# MM32_Class_board_V2_0.net
KiCad netlist of a schematic drawn in Altium Designer
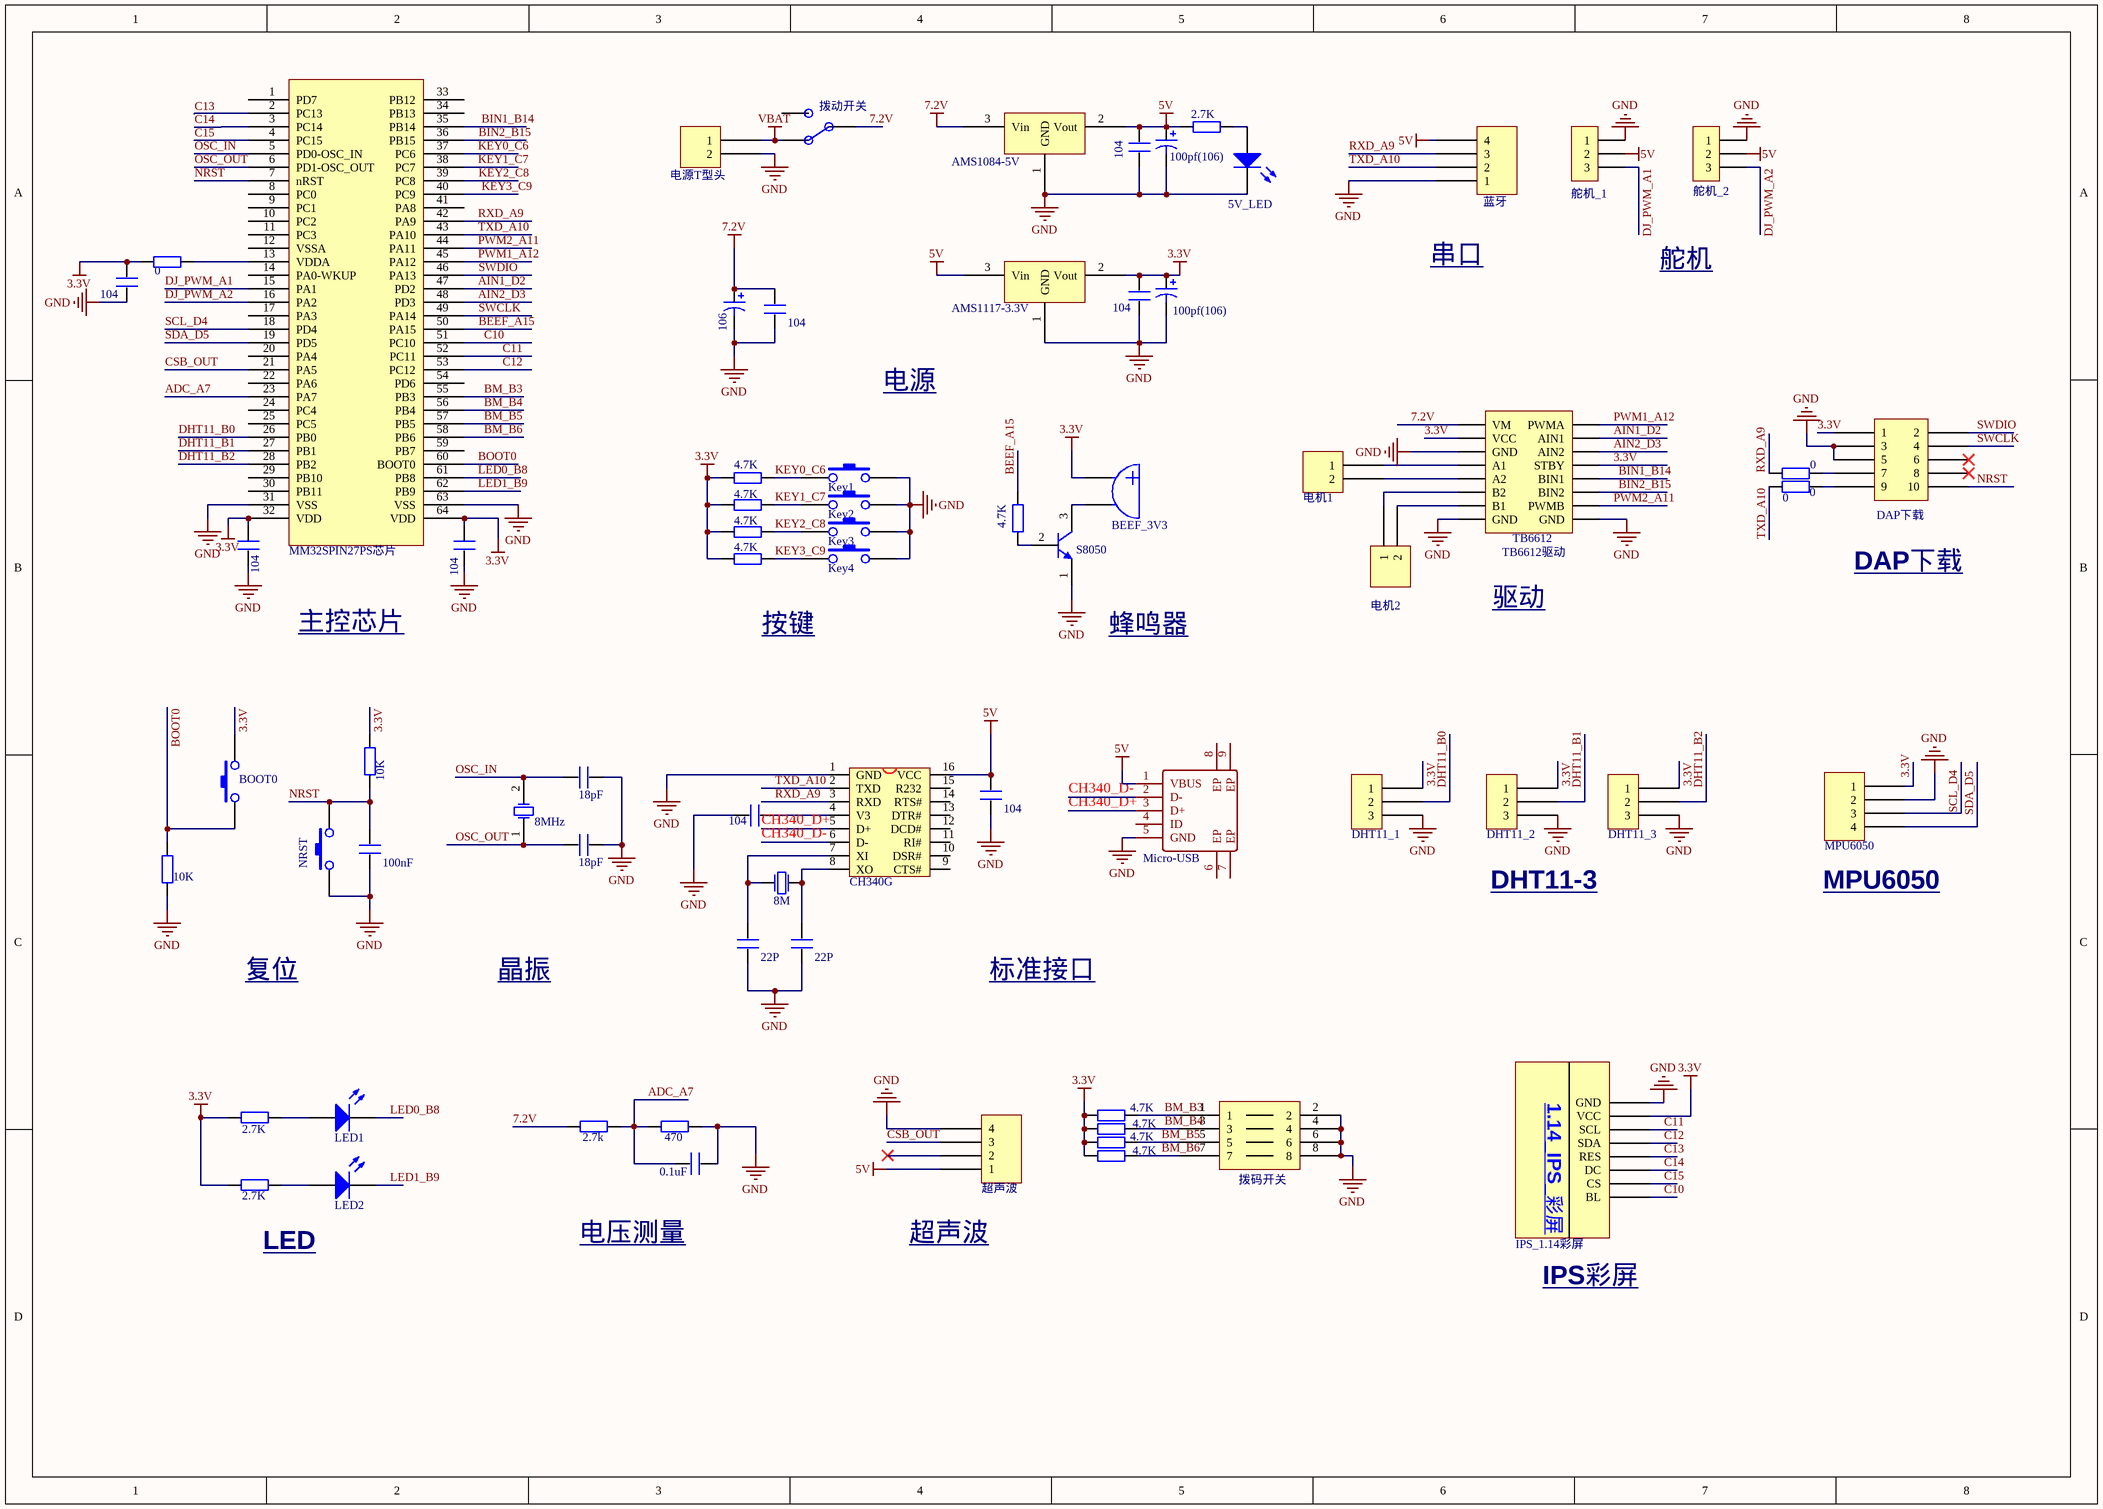
[diagram p0: MM32_Class_board_V2.0.SchDoc]

(export (version "E")
  (design (tool "Eeschema 10.0.6"))
  (components
    (comp (ref "*1")
      (value "IPS_1.14彩屏")
      (footprint "1.14_IPS")
      (libsource (lib "DZB原理图库") (part "IPS_1.14彩屏"))
    )
    (comp (ref "6050")
      (value "MPU6050")
      (footprint "四脚插座")
      (description "四脚插座")
      (libsource (lib "") (part "P4_1"))
    )
    (comp (ref "A1")
      (value "AMS1117-3.3V")
      (footprint "AMS1117")
      (libsource (lib "DZB原理图库") (part "AMS1117"))
    )
    (comp (ref "A2")
      (value "AMS1084-5V")
      (footprint "AMS1086")
      (description "5.0V")
      (libsource (lib "DZB原理图库") (part "AMS1084"))
    )
    (comp (ref "B1") (value "BEEF_3V3") (footprint "BEEF_3V3") (libsource (lib "DZB原理图库") (part "BEEF_3V3")))
    (comp (ref "BOOT0")
      (value "BOOT0")
      (footprint "贴片按键")
      (description "按键")
      (libsource (lib "DZB原理图库") (part "Key"))
    )
    (comp (ref "C1")
      (value "104")
      (footprint "电容0805")
      (description "贴片电容")
      (libsource (lib "DZB原理图库") (part "C电容"))
    )
    (comp (ref "C2")
      (value "100pf(106)")
      (footprint "钽电容1206")
      (description "钽电容")
      (fields (field (name "PUBLISHER") "Altium Limited"))
      (libsource (lib "DZB原理图库") (part "C极性电容"))
    )
    (comp (ref "C3")
      (value "104")
      (footprint "电容0805")
      (description "贴片电容")
      (libsource (lib "DZB原理图库") (part "C电容"))
    )
    (comp (ref "C4")
      (value "104")
      (footprint "电容0805")
      (description "贴片电容")
      (libsource (lib "DZB原理图库") (part "C电容"))
    )
    (comp (ref "C5")
      (value "100pf(106)")
      (footprint "钽电容1206")
      (description "钽电容")
      (fields (field (name "PUBLISHER") "Altium Limited"))
      (libsource (lib "DZB原理图库") (part "C极性电容"))
    )
    (comp (ref "C6")
      (value "106")
      (footprint "钽电容1206")
      (description "钽电容")
      (fields (field (name "PUBLISHER") "Altium Limited"))
      (libsource (lib "DZB原理图库") (part "C极性电容"))
    )
    (comp (ref "C7")
      (value "104")
      (footprint "电容0805")
      (description "贴片电容")
      (libsource (lib "DZB原理图库") (part "C电容"))
    )
    (comp (ref "C8")
      (value "104")
      (footprint "电容0805")
      (description "贴片电容")
      (libsource (lib "DZB原理图库") (part "C电容"))
    )
    (comp (ref "C9")
      (value "104")
      (footprint "电容0805")
      (description "贴片电容")
      (libsource (lib "DZB原理图库") (part "C电容"))
    )
    (comp (ref "C10")
      (value "18pF")
      (footprint "电容0805")
      (description "贴片电容")
      (libsource (lib "DZB原理图库") (part "C电容"))
    )
    (comp (ref "C11")
      (value "104")
      (footprint "电容0805")
      (description "贴片电容")
      (libsource (lib "LYF") (part "C电容"))
    )
    (comp (ref "C12")
      (value "104")
      (footprint "电容0805")
      (description "贴片电容")
      (libsource (lib "LYF") (part "C电容"))
    )
    (comp (ref "C13")
      (value "18pF")
      (footprint "电容0805")
      (description "贴片电容")
      (libsource (lib "DZB原理图库") (part "C电容"))
    )
    (comp (ref "C15")
      (value "22P")
      (footprint "电容0805")
      (description "贴片电容")
      (libsource (lib "LYF") (part "C电容"))
    )
    (comp (ref "C16")
      (value "22P")
      (footprint "电容0805")
      (description "贴片电容")
      (libsource (lib "LYF") (part "C电容"))
    )
    (comp (ref "C17")
      (value "0.1uF")
      (footprint "电容0805")
      (description "贴片电容")
      (libsource (lib "DZB原理图库") (part "C电容"))
    )
    (comp (ref "D1")
      (value "5V_LED")
      (footprint "LED贴片")
      (description "Typical RED, GREEN, YELLOW, AMBER GaAs LED")
      (fields (field (name "PUBLISHER") "Altium Limited"))
      (libsource (lib "DZB原理图库") (part "LED"))
    )
    (comp (ref "D2")
      (value "LED1")
      (footprint "LED贴片")
      (description "Typical RED, GREEN, YELLOW, AMBER GaAs LED")
      (fields (field (name "PUBLISHER") "Altium Limited"))
      (libsource (lib "DZB原理图库") (part "LED"))
    )
    (comp (ref "D3")
      (value "LED2")
      (footprint "LED贴片")
      (description "Typical RED, GREEN, YELLOW, AMBER GaAs LED")
      (fields (field (name "PUBLISHER") "Altium Limited"))
      (libsource (lib "DZB原理图库") (part "LED"))
    )
    (comp (ref "DAP下载") (value "DAP下载") (footprint "P5X2") (libsource (lib "1") (part "P5X2")))
    (comp (ref "K_C6")
      (value "Key1")
      (footprint "贴片按键")
      (description "按键")
      (libsource (lib "DZB原理图库") (part "Key"))
    )
    (comp (ref "K_C7")
      (value "Key2")
      (footprint "贴片按键")
      (description "按键")
      (libsource (lib "DZB原理图库") (part "Key"))
    )
    (comp (ref "K_C8")
      (value "Key3")
      (footprint "贴片按键")
      (description "按键")
      (libsource (lib "DZB原理图库") (part "Key"))
    )
    (comp (ref "K_C9")
      (value "Key4")
      (footprint "贴片按键")
      (description "按键")
      (libsource (lib "DZB原理图库") (part "Key"))
    )
    (comp (ref "M1")
      (value "Micro-USB")
      (footprint "Micro-USB")
      (description "链接：https://item.taobao.com/item.htm?_u=338ue8lj7060&id=619776041547")
      (libsource (lib "DZB原理图库") (part "Micro-USB"))
    )
    (comp (ref "OS1") (value "8M") (footprint "晶振") (libsource (lib "LYF") (part "晶振")))
    (comp (ref "P4")
      (value "DHT11_1")
      (footprint "三脚插座")
      (description "三脚插座")
      (libsource (lib "DZB原理图库") (part "P3"))
    )
    (comp (ref "P5")
      (value "DHT11_2")
      (footprint "三脚插座")
      (description "三脚插座")
      (libsource (lib "DZB原理图库") (part "P3"))
    )
    (comp (ref "P6")
      (value "DHT11_3")
      (footprint "三脚插座")
      (description "三脚插座")
      (libsource (lib "DZB原理图库") (part "P3"))
    )
    (comp (ref "PA1")
      (value "电机1")
      (footprint "电源插座1")
      (description "接线端子")
      (libsource (lib "") (part "POWERA_1"))
    )
    (comp (ref "PA2")
      (value "电机2")
      (footprint "电源插座1")
      (description "接线端子")
      (libsource (lib "DZB原理图库") (part "POWERA"))
    )
    (comp (ref "PB1")
      (value "电源T型头")
      (footprint "电源插座2")
      (description "电源插座B")
      (libsource (lib "1") (part "T型头"))
    )
    (comp (ref "Q1")
      (value "S8050")
      (footprint "NPN8050")
      (description "NPN三极管")
      (fields (field (name "PUBLISHER") "Altium Limited"))
      (libsource (lib "DZB原理图库") (part "S8050"))
    )
    (comp (ref "R1")
      (value "2.7K")
      (footprint "电阻0805")
      (description "贴片电阻")
      (fields (field (name "PUBLISHER") "Altium Limited"))
      (libsource (lib "DZB原理图库") (part "Res1"))
    )
    (comp (ref "R2")
      (value "0")
      (footprint "电阻0805")
      (description "贴片电阻")
      (fields (field (name "PUBLISHER") "Altium Limited"))
      (libsource (lib "DZB原理图库") (part "Res"))
    )
    (comp (ref "R3")
      (value "4.7K")
      (footprint "电阻0805")
      (description "贴片电阻")
      (fields (field (name "PUBLISHER") "Altium Limited"))
      (libsource (lib "DZB原理图库") (part "Res1"))
    )
    (comp (ref "R4")
      (value "4.7K")
      (footprint "电阻0805")
      (description "贴片电阻")
      (fields (field (name "PUBLISHER") "Altium Limited"))
      (libsource (lib "DZB原理图库") (part "Res1"))
    )
    (comp (ref "R5")
      (value "4.7K")
      (footprint "电阻0805")
      (description "贴片电阻")
      (fields (field (name "PUBLISHER") "Altium Limited"))
      (libsource (lib "") (part "Res1_1"))
    )
    (comp (ref "R6")
      (value "4.7K")
      (footprint "电阻0805")
      (description "贴片电阻")
      (fields (field (name "PUBLISHER") "Altium Limited"))
      (libsource (lib "DZB原理图库") (part "Res1"))
    )
    (comp (ref "R7")
      (value "4.7K")
      (footprint "电阻0805")
      (description "贴片电阻")
      (fields (field (name "PUBLISHER") "Altium Limited"))
      (libsource (lib "DZB原理图库") (part "Res1"))
    )
    (comp (ref "R8")
      (value "10K")
      (footprint "电阻0805")
      (description "贴片电阻")
      (fields (field (name "PUBLISHER") "Altium Limited"))
      (libsource (lib "") (part "Res_2"))
    )
    (comp (ref "R9")
      (value "10K")
      (footprint "电阻0805")
      (description "贴片电阻")
      (fields (field (name "PUBLISHER") "Altium Limited"))
      (libsource (lib "") (part "Res_2"))
    )
    (comp (ref "R10")
      (value "0")
      (footprint "电阻0805")
      (description "贴片电阻")
      (fields (field (name "PUBLISHER") "Altium Limited"))
      (libsource (lib "DZB原理图库") (part "Res"))
    )
    (comp (ref "R11")
      (value "0")
      (footprint "电阻0805")
      (description "贴片电阻")
      (fields (field (name "ALTIUM_VALUE") "0") (field (name "PUBLISHER") "Altium Limited"))
      (libsource (lib "") (part "Res_1"))
    )
    (comp (ref "R12")
      (value "2.7K")
      (footprint "电阻0805")
      (description "贴片电阻")
      (fields (field (name "PUBLISHER") "Altium Limited"))
      (libsource (lib "DZB原理图库") (part "Res"))
    )
    (comp (ref "R13")
      (value "2.7k")
      (footprint "电阻0805")
      (description "贴片电阻")
      (fields (field (name "PUBLISHER") "Altium Limited"))
      (libsource (lib "DZB原理图库") (part "Res"))
    )
    (comp (ref "R14")
      (value "470")
      (footprint "电阻0805")
      (description "10K")
      (fields (field (name "PUBLISHER") "Altium Limited"))
      (libsource (lib "DZB原理图库") (part "Res"))
    )
    (comp (ref "R15")
      (value "2.7K")
      (footprint "电阻0805")
      (description "贴片电阻")
      (fields (field (name "PUBLISHER") "Altium Limited"))
      (libsource (lib "DZB原理图库") (part "Res"))
    )
    (comp (ref "R16")
      (value "4.7K")
      (footprint "电阻0805")
      (description "贴片电阻")
      (fields (field (name "PUBLISHER") "Altium Limited"))
      (libsource (lib "DZB原理图库") (part "Res1"))
    )
    (comp (ref "R17")
      (value "4.7K")
      (footprint "电阻0805")
      (description "贴片电阻")
      (fields (field (name "PUBLISHER") "Altium Limited"))
      (libsource (lib "DZB原理图库") (part "Res1"))
    )
    (comp (ref "R18")
      (value "4.7K")
      (footprint "电阻0805")
      (description "贴片电阻")
      (fields (field (name "PUBLISHER") "Altium Limited"))
      (libsource (lib "DZB原理图库") (part "Res1"))
    )
    (comp (ref "R19")
      (value "4.7K")
      (footprint "电阻0805")
      (description "贴片电阻")
      (fields (field (name "PUBLISHER") "Altium Limited"))
      (libsource (lib "DZB原理图库") (part "Res1"))
    )
    (comp (ref "RESET")
      (value "100nF")
      (footprint "电容0805")
      (description "贴片电容")
      (libsource (lib "DZB原理图库") (part "C电容"))
    )
    (comp (ref "S1") (value "拨动开关") (footprint "拨动开关直插") (libsource (lib "V4.0_ZK") (part "拨动开关")))
    (comp (ref "S7")
      (value "NRST")
      (footprint "贴片按键")
      (description "按键")
      (libsource (lib "DZB原理图库") (part "Key"))
    )
    (comp (ref "U1")
      (value "MM32SPIN27PS芯片")
      (footprint "LQFP-64_L10.0-W10.0-P0.50-LS12.0-BL")
      (description "MM32SPIN27PS芯片封装")
      (libsource (lib "DZB原理图库") (part "MM32SPIN27PS"))
    )
    (comp (ref "U2")
      (value "TB6612驱动")
      (footprint "6612pcb")
      (description "小型电机驱动")
      (libsource (lib "DZB原理图库") (part "TB6612"))
    )
    (comp (ref "U3")
      (value "CH340G")
      (footprint "CH340G")
      (description "USB2UART")
      (libsource (lib "LYF") (part "CH340G"))
    )
    (comp (ref "Y1")
      (value "8MHz")
      (footprint "晶振")
      (description "晶振")
      (fields (field (name "PUBLISHER") "Altium Limited"))
      (libsource (lib "DZB原理图库") (part "XTAL"))
    )
    (comp (ref "串口") (value "蓝牙") (footprint "四脚插座") (libsource (lib "DZB原理图库") (part "P4")))
    (comp (ref "拨码开关") (value "拨码开关") (footprint "拨码开关") (libsource (lib "1") (part "拨码开关")))
    (comp (ref "舵机1") (value "舵机_1") (footprint "P3") (libsource (lib "1") (part "P3")))
    (comp (ref "舵机2") (value "舵机_2") (footprint "P3") (libsource (lib "1") (part "P3")))
    (comp (ref "超声波")
      (value "超声波")
      (footprint "四脚插座")
      (description "四脚插座")
      (libsource (lib "DZB原理图库") (part "P4"))
    )
  )
  (nets
    (net (code "1") (name "/ADC_A7") (class "Default")
      (node (ref "C17") (pin "1") (pintype "passive"))
      (node (ref "R13") (pin "2") (pinfunction "2_2") (pintype "passive"))
      (node (ref "R14") (pin "1") (pinfunction "1_1") (pintype "passive"))
      (node (ref "U1") (pin "23") (pinfunction "PA7_23") (pintype "passive"))
    )
    (net (code "2") (name "/AIN1_D2") (class "Default")
      (node (ref "U1") (pin "47") (pinfunction "PD2_47") (pintype "passive"))
      (node (ref "U2") (pin "10") (pinfunction "AIN1_10") (pintype "passive"))
    )
    (net (code "3") (name "/AIN2_D3") (class "Default")
      (node (ref "U1") (pin "48") (pinfunction "PD3_48") (pintype "passive"))
      (node (ref "U2") (pin "11") (pinfunction "AIN2_11") (pintype "passive"))
    )
    (net (code "4") (name "/BEEF_A15") (class "Default")
      (node (ref "R5") (pin "1") (pinfunction "1_1") (pintype "passive"))
      (node (ref "U1") (pin "50") (pinfunction "PA15_50") (pintype "passive"))
    )
    (net (code "5") (name "/BIN1_B14") (class "Default")
      (node (ref "U1") (pin "35") (pinfunction "PB14_35") (pintype "passive"))
      (node (ref "U2") (pin "13") (pinfunction "BIN1_13") (pintype "passive"))
    )
    (net (code "6") (name "/BIN2_B15") (class "Default")
      (node (ref "U1") (pin "36") (pinfunction "PB15_36") (pintype "passive"))
      (node (ref "U2") (pin "14") (pinfunction "BIN2_14") (pintype "passive"))
    )
    (net (code "7") (name "/BM_B3") (class "Default")
      (node (ref "R16") (pin "2") (pinfunction "2_2") (pintype "passive"))
      (node (ref "U1") (pin "55") (pinfunction "PB3_55") (pintype "passive"))
      (node (ref "拨码开关") (pin "1") (pinfunction "1_1") (pintype "passive"))
    )
    (net (code "8") (name "/BM_B4") (class "Default")
      (node (ref "R17") (pin "2") (pinfunction "2_2") (pintype "passive"))
      (node (ref "U1") (pin "56") (pinfunction "PB4_56") (pintype "passive"))
      (node (ref "拨码开关") (pin "3") (pinfunction "3_3") (pintype "passive"))
    )
    (net (code "9") (name "/BM_B5") (class "Default")
      (node (ref "R18") (pin "2") (pinfunction "2_2") (pintype "passive"))
      (node (ref "U1") (pin "57") (pinfunction "PB5_57") (pintype "passive"))
      (node (ref "拨码开关") (pin "5") (pinfunction "5_5") (pintype "passive"))
    )
    (net (code "10") (name "/BM_B6") (class "Default")
      (node (ref "R19") (pin "2") (pinfunction "2_2") (pintype "passive"))
      (node (ref "U1") (pin "58") (pinfunction "PB6_58") (pintype "passive"))
      (node (ref "拨码开关") (pin "7") (pinfunction "7_7") (pintype "passive"))
    )
    (net (code "11") (name "/BOOT0") (class "Default")
      (node (ref "BOOT0") (pin "1") (pinfunction "1_1") (pintype "passive"))
      (node (ref "R9") (pin "2") (pinfunction "2_2") (pintype "passive"))
      (node (ref "U1") (pin "60") (pinfunction "BOOT0_60") (pintype "passive"))
    )
    (net (code "12") (name "/C10") (class "Default")
      (node (ref "*1") (pin "8") (pinfunction "BL_8") (pintype "passive"))
      (node (ref "U1") (pin "51") (pinfunction "PC10_51") (pintype "passive"))
    )
    (net (code "13") (name "/C11") (class "Default")
      (node (ref "*1") (pin "3") (pinfunction "SCL_3") (pintype "passive"))
      (node (ref "U1") (pin "52") (pinfunction "PC11_52") (pintype "passive"))
    )
    (net (code "14") (name "/C12") (class "Default")
      (node (ref "*1") (pin "4") (pinfunction "SDA_4") (pintype "passive"))
      (node (ref "U1") (pin "53") (pinfunction "PC12_53") (pintype "passive"))
    )
    (net (code "15") (name "/C13") (class "Default")
      (node (ref "*1") (pin "5") (pinfunction "RES_5") (pintype "passive"))
      (node (ref "U1") (pin "2") (pinfunction "PC13_2") (pintype "passive"))
    )
    (net (code "16") (name "/C14") (class "Default")
      (node (ref "*1") (pin "6") (pinfunction "DC_6") (pintype "passive"))
      (node (ref "U1") (pin "3") (pinfunction "PC14_3") (pintype "passive"))
    )
    (net (code "17") (name "/C15") (class "Default")
      (node (ref "*1") (pin "7") (pinfunction "CS_7") (pintype "passive"))
      (node (ref "U1") (pin "4") (pinfunction "PC15_4") (pintype "passive"))
    )
    (net (code "18") (name "/CH340_D+") (class "Default")
      (node (ref "M1") (pin "3") (pinfunction "D+_3") (pintype "passive"))
      (node (ref "U3") (pin "5") (pinfunction "D+_5") (pintype "passive"))
    )
    (net (code "19") (name "/CH340_D-") (class "Default")
      (node (ref "M1") (pin "2") (pinfunction "D-_2") (pintype "passive"))
      (node (ref "U3") (pin "6") (pinfunction "D-_6") (pintype "passive"))
    )
    (net (code "20") (name "/CSB_OUT") (class "Default")
      (node (ref "U1") (pin "21") (pinfunction "PA5_21") (pintype "passive"))
      (node (ref "超声波") (pin "3") (pinfunction "3_3") (pintype "passive"))
    )
    (net (code "21") (name "/DHT11_B0") (class "Default")
      (node (ref "P4") (pin "2") (pinfunction "2_2") (pintype "passive"))
      (node (ref "U1") (pin "26") (pinfunction "PB0_26") (pintype "passive"))
    )
    (net (code "22") (name "/DHT11_B1") (class "Default")
      (node (ref "P5") (pin "2") (pinfunction "2_2") (pintype "passive"))
      (node (ref "U1") (pin "27") (pinfunction "PB1_27") (pintype "passive"))
    )
    (net (code "23") (name "/DHT11_B2") (class "Default")
      (node (ref "P6") (pin "2") (pinfunction "2_2") (pintype "passive"))
      (node (ref "U1") (pin "28") (pinfunction "PB2_28") (pintype "passive"))
    )
    (net (code "24") (name "/DJ_PWM_A1") (class "Default")
      (node (ref "U1") (pin "15") (pinfunction "PA1_15") (pintype "passive"))
      (node (ref "舵机1") (pin "3") (pinfunction "3_3") (pintype "passive"))
    )
    (net (code "25") (name "/DJ_PWM_A2") (class "Default")
      (node (ref "U1") (pin "16") (pinfunction "PA2_16") (pintype "passive"))
      (node (ref "舵机2") (pin "3") (pinfunction "3_3") (pintype "passive"))
    )
    (net (code "26") (name "/KEY0_C6") (class "Default")
      (node (ref "K_C6") (pin "1") (pinfunction "1_1") (pintype "passive"))
      (node (ref "R3") (pin "2") (pinfunction "2_2") (pintype "passive"))
      (node (ref "U1") (pin "37") (pinfunction "PC6_37") (pintype "passive"))
    )
    (net (code "27") (name "/KEY1_C7") (class "Default")
      (node (ref "K_C7") (pin "1") (pinfunction "1_1") (pintype "passive"))
      (node (ref "R4") (pin "2") (pinfunction "2_2") (pintype "passive"))
      (node (ref "U1") (pin "38") (pinfunction "PC7_38") (pintype "passive"))
    )
    (net (code "28") (name "/KEY2_C8") (class "Default")
      (node (ref "K_C8") (pin "1") (pinfunction "1_1") (pintype "passive"))
      (node (ref "R6") (pin "2") (pinfunction "2_2") (pintype "passive"))
      (node (ref "U1") (pin "39") (pinfunction "PC8_39") (pintype "passive"))
    )
    (net (code "29") (name "/KEY3_C9") (class "Default")
      (node (ref "K_C9") (pin "1") (pinfunction "1_1") (pintype "passive"))
      (node (ref "R7") (pin "2") (pinfunction "2_2") (pintype "passive"))
      (node (ref "U1") (pin "40") (pinfunction "PC9_40") (pintype "passive"))
    )
    (net (code "30") (name "/LED0_B8") (class "Default")
      (node (ref "D2") (pin "2") (pinfunction "K_2") (pintype "passive"))
      (node (ref "U1") (pin "61") (pinfunction "PB8_61") (pintype "passive"))
    )
    (net (code "31") (name "/LED1_B9") (class "Default")
      (node (ref "D3") (pin "2") (pinfunction "K_2") (pintype "passive"))
      (node (ref "U1") (pin "62") (pinfunction "PB9_62") (pintype "passive"))
    )
    (net (code "32") (name "/NRST") (class "Default")
      (node (ref "DAP下载") (pin "10") (pinfunction "10_10") (pintype "passive"))
      (node (ref "R8") (pin "1") (pinfunction "1_1") (pintype "passive"))
      (node (ref "RESET") (pin "2") (pintype "passive"))
      (node (ref "S7") (pin "2") (pinfunction "2_2") (pintype "passive"))
      (node (ref "U1") (pin "7") (pinfunction "nRST_7") (pintype "passive"))
    )
    (net (code "33") (name "/OSC_IN") (class "Default")
      (node (ref "C10") (pin "1") (pintype "passive"))
      (node (ref "U1") (pin "5") (pinfunction "PD0-OSC_IN_5") (pintype "passive"))
      (node (ref "Y1") (pin "2") (pinfunction "OSC2_2") (pintype "passive"))
    )
    (net (code "34") (name "/OSC_OUT") (class "Default")
      (node (ref "C13") (pin "2") (pintype "passive"))
      (node (ref "U1") (pin "6") (pinfunction "PD1-OSC_OUT_6") (pintype "passive"))
      (node (ref "Y1") (pin "1") (pinfunction "OSC1_1") (pintype "passive"))
    )
    (net (code "35") (name "/PWM1_A12") (class "Default")
      (node (ref "U1") (pin "45") (pinfunction "PA12_45") (pintype "passive"))
      (node (ref "U2") (pin "9") (pinfunction "PWMA_9") (pintype "passive"))
    )
    (net (code "36") (name "/PWM2_A11") (class "Default")
      (node (ref "U1") (pin "44") (pinfunction "PA11_44") (pintype "passive"))
      (node (ref "U2") (pin "15") (pinfunction "PWMB_15") (pintype "passive"))
    )
    (net (code "37") (name "/RXD_A9") (class "Default")
      (node (ref "R10") (pin "1") (pinfunction "1_1") (pintype "passive"))
      (node (ref "U1") (pin "42") (pinfunction "PA9_42") (pintype "passive"))
      (node (ref "U3") (pin "3") (pinfunction "RXD_3") (pintype "passive"))
      (node (ref "串口") (pin "3") (pinfunction "3_3") (pintype "passive"))
    )
    (net (code "38") (name "/SCL_D4") (class "Default")
      (node (ref "6050") (pin "3") (pinfunction "3_3") (pintype "passive"))
      (node (ref "U1") (pin "18") (pinfunction "PD4_18") (pintype "passive"))
    )
    (net (code "39") (name "/SDA_D5") (class "Default")
      (node (ref "6050") (pin "4") (pinfunction "4_4") (pintype "passive"))
      (node (ref "U1") (pin "19") (pinfunction "PD5_19") (pintype "passive"))
    )
    (net (code "40") (name "/SWCLK") (class "Default")
      (node (ref "DAP下载") (pin "4") (pinfunction "4_4") (pintype "passive"))
      (node (ref "U1") (pin "49") (pinfunction "PA14_49") (pintype "passive"))
    )
    (net (code "41") (name "/SWDIO") (class "Default")
      (node (ref "DAP下载") (pin "2") (pinfunction "2_2") (pintype "passive"))
      (node (ref "U1") (pin "46") (pinfunction "PA13_46") (pintype "passive"))
    )
    (net (code "42") (name "/TXD_A10") (class "Default")
      (node (ref "R11") (pin "2") (pinfunction "2_2") (pintype "passive"))
      (node (ref "U1") (pin "43") (pinfunction "PA10_43") (pintype "passive"))
      (node (ref "U3") (pin "2") (pinfunction "TXD_2") (pintype "passive"))
      (node (ref "串口") (pin "2") (pinfunction "2_2") (pintype "passive"))
    )
    (net (code "43") (name "3.3V") (class "Default")
      (node (ref "*1") (pin "2") (pinfunction "VCC_2") (pintype "passive"))
      (node (ref "6050") (pin "1") (pinfunction "1_1") (pintype "passive"))
      (node (ref "A1") (pin "2") (pinfunction "Vout_2") (pintype "passive"))
      (node (ref "B1") (pin "1") (pinfunction "A_1") (pintype "passive"))
      (node (ref "BOOT0") (pin "2") (pinfunction "2_2") (pintype "passive"))
      (node (ref "C3") (pin "2") (pintype "passive"))
      (node (ref "C4") (pin "2") (pintype "passive"))
      (node (ref "C5") (pin "1") (pinfunction "1_1") (pintype "passive"))
      (node (ref "C8") (pin "2") (pintype "passive"))
      (node (ref "C9") (pin "2") (pintype "passive"))
      (node (ref "DAP下载") (pin "1") (pinfunction "1_1") (pintype "passive"))
      (node (ref "P4") (pin "1") (pinfunction "1_1") (pintype "passive"))
      (node (ref "P5") (pin "1") (pinfunction "1_1") (pintype "passive"))
      (node (ref "P6") (pin "1") (pinfunction "1_1") (pintype "passive"))
      (node (ref "R12") (pin "1") (pinfunction "1_1") (pintype "passive"))
      (node (ref "R15") (pin "1") (pinfunction "1_1") (pintype "passive"))
      (node (ref "R16") (pin "1") (pinfunction "1_1") (pintype "passive"))
      (node (ref "R17") (pin "1") (pinfunction "1_1") (pintype "passive"))
      (node (ref "R18") (pin "1") (pinfunction "1_1") (pintype "passive"))
      (node (ref "R19") (pin "1") (pinfunction "1_1") (pintype "passive"))
      (node (ref "R2") (pin "1") (pinfunction "1_1") (pintype "passive"))
      (node (ref "R3") (pin "1") (pinfunction "1_1") (pintype "passive"))
      (node (ref "R4") (pin "1") (pinfunction "1_1") (pintype "passive"))
      (node (ref "R6") (pin "1") (pinfunction "1_1") (pintype "passive"))
      (node (ref "R7") (pin "1") (pinfunction "1_1") (pintype "passive"))
      (node (ref "R8") (pin "2") (pinfunction "2_2") (pintype "passive"))
      (node (ref "U1") (pin "32") (pinfunction "VDD_32") (pintype "passive"))
      (node (ref "U1") (pin "64") (pinfunction "VDD_64") (pintype "passive"))
      (node (ref "U2") (pin "12") (pinfunction "STBY_12") (pintype "passive"))
      (node (ref "U2") (pin "2") (pinfunction "VCC_2") (pintype "passive"))
    )
    (net (code "44") (name "5V") (class "Default")
      (node (ref "A1") (pin "3") (pinfunction "Vin_3") (pintype "passive"))
      (node (ref "A2") (pin "2") (pinfunction "Vout_2") (pintype "passive"))
      (node (ref "C1") (pin "2") (pintype "passive"))
      (node (ref "C12") (pin "2") (pintype "passive"))
      (node (ref "C2") (pin "1") (pinfunction "1_1") (pintype "passive"))
      (node (ref "M1") (pin "1") (pinfunction "VBUS_1") (pintype "passive"))
      (node (ref "R1") (pin "1") (pinfunction "1_1") (pintype "passive"))
      (node (ref "U3") (pin "16") (pinfunction "VCC_16") (pintype "passive"))
      (node (ref "串口") (pin "4") (pinfunction "4_4") (pintype "passive"))
      (node (ref "舵机1") (pin "2") (pinfunction "2_2") (pintype "passive"))
      (node (ref "舵机2") (pin "2") (pinfunction "2_2") (pintype "passive"))
      (node (ref "超声波") (pin "1") (pinfunction "1_1") (pintype "passive"))
    )
    (net (code "45") (name "7.2V") (class "Default")
      (node (ref "A2") (pin "3") (pinfunction "Vin_3") (pintype "passive"))
      (node (ref "C6") (pin "1") (pinfunction "1_1") (pintype "passive"))
      (node (ref "C7") (pin "2") (pintype "passive"))
      (node (ref "R13") (pin "1") (pinfunction "1_1") (pintype "passive"))
      (node (ref "S1") (pin "2") (pinfunction "2_2") (pintype "passive"))
      (node (ref "U2") (pin "1") (pinfunction "VM_1") (pintype "passive"))
    )
    (net (code "46") (name "GND") (class "Default")
      (node (ref "*1") (pin "1") (pinfunction "GND_1") (pintype "passive"))
      (node (ref "6050") (pin "2") (pinfunction "2_2") (pintype "passive"))
      (node (ref "A1") (pin "1") (pinfunction "GND_1") (pintype "passive"))
      (node (ref "A2") (pin "1") (pinfunction "GND_1") (pintype "passive"))
      (node (ref "C1") (pin "1") (pintype "passive"))
      (node (ref "C10") (pin "2") (pintype "passive"))
      (node (ref "C11") (pin "1") (pintype "passive"))
      (node (ref "C12") (pin "1") (pintype "passive"))
      (node (ref "C13") (pin "1") (pintype "passive"))
      (node (ref "C15") (pin "1") (pintype "passive"))
      (node (ref "C16") (pin "1") (pintype "passive"))
      (node (ref "C17") (pin "2") (pintype "passive"))
      (node (ref "C2") (pin "2") (pinfunction "2_2") (pintype "passive"))
      (node (ref "C3") (pin "1") (pintype "passive"))
      (node (ref "C4") (pin "1") (pintype "passive"))
      (node (ref "C5") (pin "2") (pinfunction "2_2") (pintype "passive"))
      (node (ref "C6") (pin "2") (pinfunction "2_2") (pintype "passive"))
      (node (ref "C7") (pin "1") (pintype "passive"))
      (node (ref "C8") (pin "1") (pintype "passive"))
      (node (ref "C9") (pin "1") (pintype "passive"))
      (node (ref "D1") (pin "2") (pinfunction "K_2") (pintype "passive"))
      (node (ref "DAP下载") (pin "3") (pinfunction "3_3") (pintype "passive"))
      (node (ref "DAP下载") (pin "5") (pinfunction "5_5") (pintype "passive"))
      (node (ref "K_C6") (pin "2") (pinfunction "2_2") (pintype "passive"))
      (node (ref "K_C7") (pin "2") (pinfunction "2_2") (pintype "passive"))
      (node (ref "K_C8") (pin "2") (pinfunction "2_2") (pintype "passive"))
      (node (ref "K_C9") (pin "2") (pinfunction "2_2") (pintype "passive"))
      (node (ref "M1") (pin "5") (pinfunction "GND_5") (pintype "passive"))
      (node (ref "P4") (pin "3") (pinfunction "3_3") (pintype "passive"))
      (node (ref "P5") (pin "3") (pinfunction "3_3") (pintype "passive"))
      (node (ref "P6") (pin "3") (pinfunction "3_3") (pintype "passive"))
      (node (ref "PB1") (pin "2") (pinfunction "2_2") (pintype "passive"))
      (node (ref "Q1") (pin "1") (pinfunction "E_1") (pintype "passive"))
      (node (ref "R14") (pin "2") (pinfunction "2_2") (pintype "passive"))
      (node (ref "R9") (pin "1") (pinfunction "1_1") (pintype "passive"))
      (node (ref "RESET") (pin "1") (pintype "passive"))
      (node (ref "S7") (pin "1") (pinfunction "1_1") (pintype "passive"))
      (node (ref "U1") (pin "31") (pinfunction "VSS_31") (pintype "passive"))
      (node (ref "U1") (pin "63") (pinfunction "VSS_63") (pintype "passive"))
      (node (ref "U2") (pin "16") (pinfunction "GND_16") (pintype "passive"))
      (node (ref "U2") (pin "3") (pinfunction "GND_3") (pintype "passive"))
      (node (ref "U2") (pin "8") (pinfunction "GND_8") (pintype "passive"))
      (node (ref "U3") (pin "1") (pinfunction "GND_1") (pintype "passive"))
      (node (ref "串口") (pin "1") (pinfunction "1_1") (pintype "passive"))
      (node (ref "拨码开关") (pin "2") (pinfunction "2_2") (pintype "passive"))
      (node (ref "拨码开关") (pin "4") (pinfunction "4_4") (pintype "passive"))
      (node (ref "拨码开关") (pin "6") (pinfunction "6_6") (pintype "passive"))
      (node (ref "拨码开关") (pin "8") (pinfunction "8_8") (pintype "passive"))
      (node (ref "舵机1") (pin "1") (pinfunction "1_1") (pintype "passive"))
      (node (ref "舵机2") (pin "1") (pinfunction "1_1") (pintype "passive"))
      (node (ref "超声波") (pin "4") (pinfunction "4_4") (pintype "passive"))
    )
    (net (code "47") (name "Net-(B1-B)") (class "Default")
      (node (ref "B1") (pin "2") (pinfunction "B_2") (pintype "passive"))
      (node (ref "Q1") (pin "3") (pinfunction "C_3") (pintype "passive"))
    )
    (net (code "48") (name "Net-(D1-A)") (class "Default")
      (node (ref "D1") (pin "1") (pinfunction "A_1") (pintype "passive"))
      (node (ref "R1") (pin "2") (pinfunction "2_2") (pintype "passive"))
    )
    (net (code "49") (name "Net-(D2-A)") (class "Default")
      (node (ref "D2") (pin "1") (pinfunction "A_1") (pintype "passive"))
      (node (ref "R12") (pin "2") (pinfunction "2_2") (pintype "passive"))
    )
    (net (code "50") (name "Net-(D3-A)") (class "Default")
      (node (ref "D3") (pin "1") (pinfunction "A_1") (pintype "passive"))
      (node (ref "R15") (pin "2") (pinfunction "2_2") (pintype "passive"))
    )
    (net (code "51") (name "Net-(DAP下载-Pad7)") (class "Default")
      (node (ref "DAP下载") (pin "7") (pinfunction "7_7") (pintype "passive"))
      (node (ref "R10") (pin "2") (pinfunction "2_2") (pintype "passive"))
    )
    (net (code "52") (name "Net-(DAP下载-Pad9)") (class "Default")
      (node (ref "DAP下载") (pin "9") (pinfunction "9_9") (pintype "passive"))
      (node (ref "R11") (pin "1") (pinfunction "1_1") (pintype "passive"))
    )
    (net (code "53") (name "Net-(OS1-P1)") (class "Default")
      (node (ref "C15") (pin "2") (pintype "passive"))
      (node (ref "OS1") (pin "1") (pinfunction "P1_1") (pintype "passive"))
      (node (ref "U3") (pin "7") (pinfunction "XI_7") (pintype "passive"))
    )
    (net (code "54") (name "Net-(OS1-P2)") (class "Default")
      (node (ref "C16") (pin "2") (pintype "passive"))
      (node (ref "OS1") (pin "2") (pinfunction "P2_2") (pintype "passive"))
      (node (ref "U3") (pin "8") (pinfunction "XO_8") (pintype "passive"))
    )
    (net (code "55") (name "Net-(Q1-B)") (class "Default")
      (node (ref "Q1") (pin "2") (pinfunction "B_2") (pintype "passive"))
      (node (ref "R5") (pin "2") (pinfunction "2_2") (pintype "passive"))
    )
    (net (code "56") (name "Net-(U1-VDDA)") (class "Default")
      (node (ref "R2") (pin "2") (pinfunction "2_2") (pintype "passive"))
      (node (ref "U1") (pin "13") (pinfunction "VDDA_13") (pintype "passive"))
    )
    (net (code "57") (name "Net-(U2-A1)") (class "Default")
      (node (ref "PA1") (pin "1") (pinfunction "1_1") (pintype "passive"))
      (node (ref "U2") (pin "4") (pinfunction "A1_4") (pintype "passive"))
    )
    (net (code "58") (name "Net-(U2-A2)") (class "Default")
      (node (ref "PA1") (pin "2") (pinfunction "2_2") (pintype "passive"))
      (node (ref "U2") (pin "5") (pinfunction "A2_5") (pintype "passive"))
    )
    (net (code "59") (name "Net-(U2-B1)") (class "Default")
      (node (ref "PA2") (pin "2") (pinfunction "2_2") (pintype "passive"))
      (node (ref "U2") (pin "7") (pinfunction "B1_7") (pintype "passive"))
    )
    (net (code "60") (name "Net-(U2-B2)") (class "Default")
      (node (ref "PA2") (pin "1") (pinfunction "1_1") (pintype "passive"))
      (node (ref "U2") (pin "6") (pinfunction "B2_6") (pintype "passive"))
    )
    (net (code "61") (name "Net-(U3-V3)") (class "Default")
      (node (ref "C11") (pin "2") (pintype "passive"))
      (node (ref "U3") (pin "4") (pinfunction "V3_4") (pintype "passive"))
    )
    (net (code "62") (name "VBAT") (class "Default")
      (node (ref "PB1") (pin "1") (pinfunction "1_1") (pintype "passive"))
      (node (ref "S1") (pin "1") (pinfunction "1_1") (pintype "passive"))
    )
    (net (code "63") (name "unconnected-(DAP下载-Pad6)") (class "Default")
      (node (ref "DAP下载") (pin "6") (pinfunction "6_6") (pintype "passive+no_connect"))
    )
    (net (code "64") (name "unconnected-(DAP下载-Pad8)") (class "Default")
      (node (ref "DAP下载") (pin "8") (pinfunction "8_8") (pintype "passive+no_connect"))
    )
    (net (code "65") (name "unconnected-(M1-EP-Pad6)") (class "Default")
      (node (ref "M1") (pin "6") (pinfunction "EP_6") (pintype "passive"))
    )
    (net (code "66") (name "unconnected-(M1-EP-Pad7)") (class "Default")
      (node (ref "M1") (pin "7") (pinfunction "EP_7") (pintype "passive"))
    )
    (net (code "67") (name "unconnected-(M1-EP-Pad8)") (class "Default")
      (node (ref "M1") (pin "8") (pinfunction "EP_8") (pintype "passive"))
    )
    (net (code "68") (name "unconnected-(M1-EP-Pad9)") (class "Default")
      (node (ref "M1") (pin "9") (pinfunction "EP_9") (pintype "passive"))
    )
    (net (code "69") (name "unconnected-(M1-ID-Pad4)") (class "Default")
      (node (ref "M1") (pin "4") (pinfunction "ID_4") (pintype "passive"))
    )
    (net (code "70") (name "unconnected-(S1-Pad3)") (class "Default")
      (node (ref "S1") (pin "3") (pinfunction "3_3") (pintype "passive"))
    )
    (net (code "71") (name "unconnected-(U1-PA0-WKUP-Pad14)") (class "Default")
      (node (ref "U1") (pin "14") (pinfunction "PA0-WKUP_14") (pintype "passive"))
    )
    (net (code "72") (name "unconnected-(U1-PA3-Pad17)") (class "Default")
      (node (ref "U1") (pin "17") (pinfunction "PA3_17") (pintype "passive"))
    )
    (net (code "73") (name "unconnected-(U1-PA4-Pad20)") (class "Default")
      (node (ref "U1") (pin "20") (pinfunction "PA4_20") (pintype "passive"))
    )
    (net (code "74") (name "unconnected-(U1-PA6-Pad22)") (class "Default")
      (node (ref "U1") (pin "22") (pinfunction "PA6_22") (pintype "passive"))
    )
    (net (code "75") (name "unconnected-(U1-PA8-Pad41)") (class "Default")
      (node (ref "U1") (pin "41") (pinfunction "PA8_41") (pintype "passive"))
    )
    (net (code "76") (name "unconnected-(U1-PB7-Pad59)") (class "Default")
      (node (ref "U1") (pin "59") (pinfunction "PB7_59") (pintype "passive"))
    )
    (net (code "77") (name "unconnected-(U1-PB10-Pad29)") (class "Default")
      (node (ref "U1") (pin "29") (pinfunction "PB10_29") (pintype "passive"))
    )
    (net (code "78") (name "unconnected-(U1-PB11-Pad30)") (class "Default")
      (node (ref "U1") (pin "30") (pinfunction "PB11_30") (pintype "passive"))
    )
    (net (code "79") (name "unconnected-(U1-PB12-Pad33)") (class "Default")
      (node (ref "U1") (pin "33") (pinfunction "PB12_33") (pintype "passive"))
    )
    (net (code "80") (name "unconnected-(U1-PB13-Pad34)") (class "Default")
      (node (ref "U1") (pin "34") (pinfunction "PB13_34") (pintype "passive"))
    )
    (net (code "81") (name "unconnected-(U1-PC0-Pad8)") (class "Default")
      (node (ref "U1") (pin "8") (pinfunction "PC0_8") (pintype "passive"))
    )
    (net (code "82") (name "unconnected-(U1-PC1-Pad9)") (class "Default")
      (node (ref "U1") (pin "9") (pinfunction "PC1_9") (pintype "passive"))
    )
    (net (code "83") (name "unconnected-(U1-PC2-Pad10)") (class "Default")
      (node (ref "U1") (pin "10") (pinfunction "PC2_10") (pintype "passive"))
    )
    (net (code "84") (name "unconnected-(U1-PC3-Pad11)") (class "Default")
      (node (ref "U1") (pin "11") (pinfunction "PC3_11") (pintype "passive"))
    )
    (net (code "85") (name "unconnected-(U1-PC4-Pad24)") (class "Default")
      (node (ref "U1") (pin "24") (pinfunction "PC4_24") (pintype "passive"))
    )
    (net (code "86") (name "unconnected-(U1-PC5-Pad25)") (class "Default")
      (node (ref "U1") (pin "25") (pinfunction "PC5_25") (pintype "passive"))
    )
    (net (code "87") (name "unconnected-(U1-PD6-Pad54)") (class "Default")
      (node (ref "U1") (pin "54") (pinfunction "PD6_54") (pintype "passive"))
    )
    (net (code "88") (name "unconnected-(U1-PD7-Pad1)") (class "Default")
      (node (ref "U1") (pin "1") (pinfunction "PD7_1") (pintype "passive"))
    )
    (net (code "89") (name "unconnected-(U1-VSSA-Pad12)") (class "Default")
      (node (ref "U1") (pin "12") (pinfunction "VSSA_12") (pintype "passive"))
    )
    (net (code "90") (name "unconnected-(U3-CTS#-Pad9)") (class "Default")
      (node (ref "U3") (pin "9") (pinfunction "CTS#_9") (pintype "passive"))
    )
    (net (code "91") (name "unconnected-(U3-DCD#-Pad12)") (class "Default")
      (node (ref "U3") (pin "12") (pinfunction "DCD#_12") (pintype "passive"))
    )
    (net (code "92") (name "unconnected-(U3-DSR#-Pad10)") (class "Default")
      (node (ref "U3") (pin "10") (pinfunction "DSR#_10") (pintype "passive"))
    )
    (net (code "93") (name "unconnected-(U3-DTR#-Pad13)") (class "Default")
      (node (ref "U3") (pin "13") (pinfunction "DTR#_13") (pintype "passive"))
    )
    (net (code "94") (name "unconnected-(U3-R232-Pad15)") (class "Default")
      (node (ref "U3") (pin "15") (pinfunction "R232_15") (pintype "passive"))
    )
    (net (code "95") (name "unconnected-(U3-RI#-Pad11)") (class "Default")
      (node (ref "U3") (pin "11") (pinfunction "RI#_11") (pintype "passive"))
    )
    (net (code "96") (name "unconnected-(U3-RTS#-Pad14)") (class "Default")
      (node (ref "U3") (pin "14") (pinfunction "RTS#_14") (pintype "passive"))
    )
    (net (code "97") (name "unconnected-(超声波-Pad2)") (class "Default")
      (node (ref "超声波") (pin "2") (pinfunction "2_2") (pintype "passive+no_connect"))
    )
  )
)
